# edgesata-v2.net
KiCad netlist of a schematic drawn in EAGLE
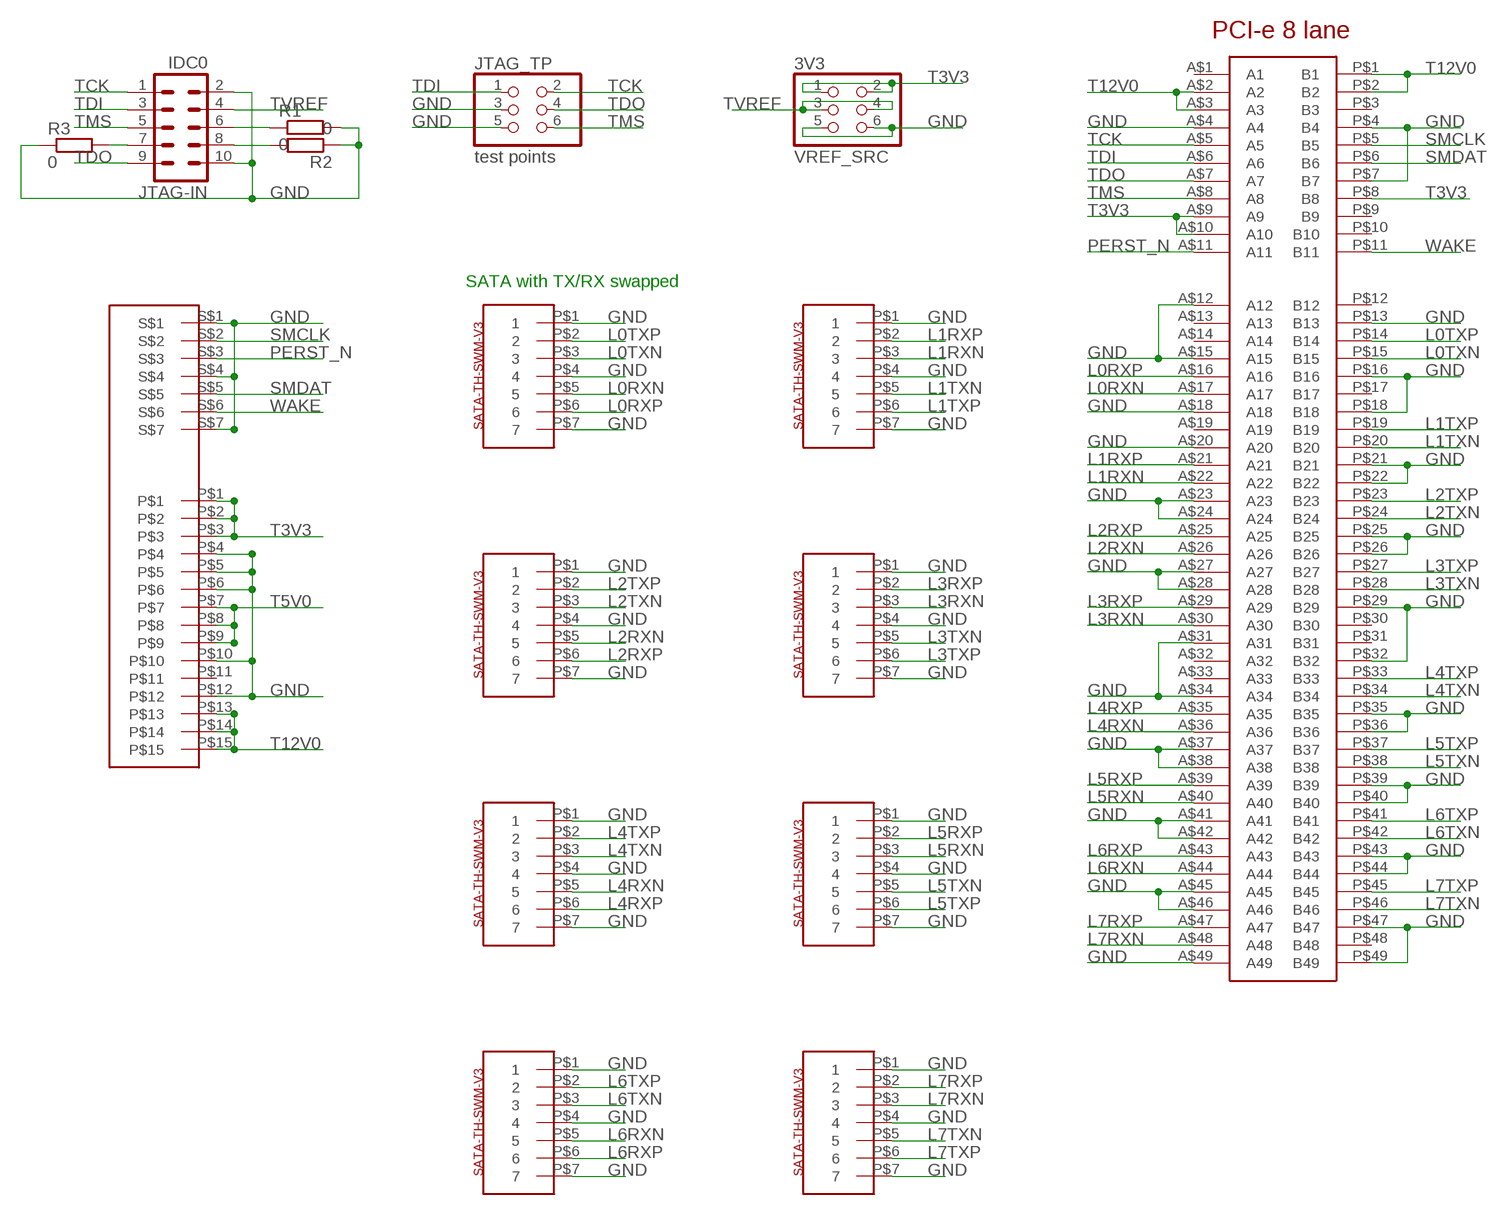
[diagram p0: schematic, sheet 1]

(export (version "E")
  (design (tool "Eeschema 10.0.6"))
  (components
    (comp (ref "3V3")
      (value "VREF_SRC")
      (footprint "eagle-import:2X03")
      (libsource (lib "eagle-import") (part "PINHD-2X3"))
    )
    (comp (ref "JTAG-IN")
      (value "IDC0")
      (footprint "eagle-import:MA05-2")
      (libsource (lib "eagle-import") (part "MA05-2"))
    )
    (comp (ref "JTAG_TP")
      (value "test points")
      (footprint "eagle-import:2X03")
      (libsource (lib "eagle-import") (part "PINHD-2X3"))
    )
    (comp (ref "LANE0")
      (value "SATA-TH-SWM-V3")
      (footprint "eagle-import:SATA-TH-SWM-V3")
      (libsource (lib "eagle-import") (part "SATA-TH-SWM-V3"))
    )
    (comp (ref "LANE1")
      (value "SATA-TH-SWM-V3")
      (footprint "eagle-import:SATA-TH-SWM-V3")
      (libsource (lib "eagle-import") (part "SATA-TH-SWM-V3"))
    )
    (comp (ref "LANE2")
      (value "SATA-TH-SWM-V3")
      (footprint "eagle-import:SATA-TH-SWM-V3")
      (libsource (lib "eagle-import") (part "SATA-TH-SWM-V3"))
    )
    (comp (ref "LANE3")
      (value "SATA-TH-SWM-V3")
      (footprint "eagle-import:SATA-TH-SWM-V3")
      (libsource (lib "eagle-import") (part "SATA-TH-SWM-V3"))
    )
    (comp (ref "LANE4")
      (value "SATA-TH-SWM-V3")
      (footprint "eagle-import:SATA-TH-SWM-V3")
      (libsource (lib "eagle-import") (part "SATA-TH-SWM-V3"))
    )
    (comp (ref "LANE5")
      (value "SATA-TH-SWM-V3")
      (footprint "eagle-import:SATA-TH-SWM-V3")
      (libsource (lib "eagle-import") (part "SATA-TH-SWM-V3"))
    )
    (comp (ref "LANE6")
      (value "SATA-TH-SWM-V3")
      (footprint "eagle-import:SATA-TH-SWM-V3")
      (libsource (lib "eagle-import") (part "SATA-TH-SWM-V3"))
    )
    (comp (ref "LANE7")
      (value "SATA-TH-SWM-V3")
      (footprint "eagle-import:SATA-TH-SWM-V3")
      (libsource (lib "eagle-import") (part "SATA-TH-SWM-V3"))
    )
    (comp (ref "R1")
      (value "0")
      (footprint "eagle-import:R0805W")
      (libsource (lib "eagle-import") (part "R-EU_R0805W"))
    )
    (comp (ref "R2")
      (value "0")
      (footprint "eagle-import:R0805W")
      (libsource (lib "eagle-import") (part "R-EU_R0805W"))
    )
    (comp (ref "R3")
      (value "0")
      (footprint "eagle-import:R0805W")
      (libsource (lib "eagle-import") (part "R-EU_R0805W"))
    )
    (comp (ref "U$1")
      (value "SATA-POWER-V1")
      (footprint "eagle-import:SATA-POWER-V1")
      (libsource (lib "eagle-import") (part "SATA-POWER-V1"))
    )
    (comp (ref "U$8")
      (value "PCIE-EDGE-8LANE-V1")
      (footprint "eagle-import:PCIE-EDGE-8LANE-V1")
      (libsource (lib "eagle-import") (part "PCIE-EDGE-8LANE-V1"))
    )
  )
  (nets
    (net (code "1") (name "/GND") (class "Default")
      (node (ref "3V3") (pin "5") (pinfunction "5_5") (pintype "passive"))
      (node (ref "3V3") (pin "6") (pinfunction "6_6") (pintype "passive"))
      (node (ref "JTAG-IN") (pin "10") (pinfunction "10_10") (pintype "passive"))
      (node (ref "JTAG-IN") (pin "2") (pinfunction "2_2") (pintype "passive"))
      (node (ref "JTAG_TP") (pin "3") (pinfunction "3_3") (pintype "passive"))
      (node (ref "JTAG_TP") (pin "5") (pinfunction "5_5") (pintype "passive"))
      (node (ref "LANE0") (pin "P$1") (pinfunction "1_P$1") (pintype "bidirectional"))
      (node (ref "LANE0") (pin "P$4") (pinfunction "4_P$4") (pintype "bidirectional"))
      (node (ref "LANE0") (pin "P$7") (pinfunction "7_P$7") (pintype "bidirectional"))
      (node (ref "LANE1") (pin "P$1") (pinfunction "1_P$1") (pintype "bidirectional"))
      (node (ref "LANE1") (pin "P$4") (pinfunction "4_P$4") (pintype "bidirectional"))
      (node (ref "LANE1") (pin "P$7") (pinfunction "7_P$7") (pintype "bidirectional"))
      (node (ref "LANE2") (pin "P$1") (pinfunction "1_P$1") (pintype "bidirectional"))
      (node (ref "LANE2") (pin "P$4") (pinfunction "4_P$4") (pintype "bidirectional"))
      (node (ref "LANE2") (pin "P$7") (pinfunction "7_P$7") (pintype "bidirectional"))
      (node (ref "LANE3") (pin "P$1") (pinfunction "1_P$1") (pintype "bidirectional"))
      (node (ref "LANE3") (pin "P$4") (pinfunction "4_P$4") (pintype "bidirectional"))
      (node (ref "LANE3") (pin "P$7") (pinfunction "7_P$7") (pintype "bidirectional"))
      (node (ref "LANE4") (pin "P$1") (pinfunction "1_P$1") (pintype "bidirectional"))
      (node (ref "LANE4") (pin "P$4") (pinfunction "4_P$4") (pintype "bidirectional"))
      (node (ref "LANE4") (pin "P$7") (pinfunction "7_P$7") (pintype "bidirectional"))
      (node (ref "LANE5") (pin "P$1") (pinfunction "1_P$1") (pintype "bidirectional"))
      (node (ref "LANE5") (pin "P$4") (pinfunction "4_P$4") (pintype "bidirectional"))
      (node (ref "LANE5") (pin "P$7") (pinfunction "7_P$7") (pintype "bidirectional"))
      (node (ref "LANE6") (pin "P$1") (pinfunction "1_P$1") (pintype "bidirectional"))
      (node (ref "LANE6") (pin "P$4") (pinfunction "4_P$4") (pintype "bidirectional"))
      (node (ref "LANE6") (pin "P$7") (pinfunction "7_P$7") (pintype "bidirectional"))
      (node (ref "LANE7") (pin "P$1") (pinfunction "1_P$1") (pintype "bidirectional"))
      (node (ref "LANE7") (pin "P$4") (pinfunction "4_P$4") (pintype "bidirectional"))
      (node (ref "LANE7") (pin "P$7") (pinfunction "7_P$7") (pintype "bidirectional"))
      (node (ref "R1") (pin "2") (pinfunction "2_2") (pintype "passive"))
      (node (ref "R2") (pin "1") (pinfunction "1_1") (pintype "passive"))
      (node (ref "R3") (pin "1") (pinfunction "1_1") (pintype "passive"))
      (node (ref "U$1") (pin "P$10") (pinfunction "P$10_P$10") (pintype "bidirectional"))
      (node (ref "U$1") (pin "P$12") (pinfunction "P$12_P$12") (pintype "bidirectional"))
      (node (ref "U$1") (pin "P$4") (pinfunction "P$4_P$4") (pintype "bidirectional"))
      (node (ref "U$1") (pin "P$5") (pinfunction "P$5_P$5") (pintype "bidirectional"))
      (node (ref "U$1") (pin "P$6") (pinfunction "P$6_P$6") (pintype "bidirectional"))
      (node (ref "U$1") (pin "S$1") (pinfunction "S$1_S$1") (pintype "bidirectional"))
      (node (ref "U$1") (pin "S$4") (pinfunction "S$4_S$4") (pintype "bidirectional"))
      (node (ref "U$1") (pin "S$7") (pinfunction "S$7_S$7") (pintype "bidirectional"))
      (node (ref "U$8") (pin "A$12") (pinfunction "A12_A$12") (pintype "bidirectional"))
      (node (ref "U$8") (pin "A$15") (pinfunction "A15_A$15") (pintype "bidirectional"))
      (node (ref "U$8") (pin "A$18") (pinfunction "A18_A$18") (pintype "bidirectional"))
      (node (ref "U$8") (pin "A$20") (pinfunction "A20_A$20") (pintype "bidirectional"))
      (node (ref "U$8") (pin "A$23") (pinfunction "A23_A$23") (pintype "bidirectional"))
      (node (ref "U$8") (pin "A$24") (pinfunction "A24_A$24") (pintype "bidirectional"))
      (node (ref "U$8") (pin "A$27") (pinfunction "A27_A$27") (pintype "bidirectional"))
      (node (ref "U$8") (pin "A$28") (pinfunction "A28_A$28") (pintype "bidirectional"))
      (node (ref "U$8") (pin "A$31") (pinfunction "A31_A$31") (pintype "bidirectional"))
      (node (ref "U$8") (pin "A$34") (pinfunction "A34_A$34") (pintype "bidirectional"))
      (node (ref "U$8") (pin "A$37") (pinfunction "A37_A$37") (pintype "bidirectional"))
      (node (ref "U$8") (pin "A$38") (pinfunction "A38_A$38") (pintype "bidirectional"))
      (node (ref "U$8") (pin "A$4") (pinfunction "A4_A$4") (pintype "bidirectional"))
      (node (ref "U$8") (pin "A$41") (pinfunction "A41_A$41") (pintype "bidirectional"))
      (node (ref "U$8") (pin "A$42") (pinfunction "A42_A$42") (pintype "bidirectional"))
      (node (ref "U$8") (pin "A$45") (pinfunction "A45_A$45") (pintype "bidirectional"))
      (node (ref "U$8") (pin "A$46") (pinfunction "A46_A$46") (pintype "bidirectional"))
      (node (ref "U$8") (pin "A$49") (pinfunction "A49_A$49") (pintype "bidirectional"))
      (node (ref "U$8") (pin "P$13") (pinfunction "B13_P$13") (pintype "bidirectional"))
      (node (ref "U$8") (pin "P$16") (pinfunction "B16_P$16") (pintype "bidirectional"))
      (node (ref "U$8") (pin "P$18") (pinfunction "B18_P$18") (pintype "bidirectional"))
      (node (ref "U$8") (pin "P$21") (pinfunction "B21_P$21") (pintype "bidirectional"))
      (node (ref "U$8") (pin "P$22") (pinfunction "B22_P$22") (pintype "bidirectional"))
      (node (ref "U$8") (pin "P$25") (pinfunction "B25_P$25") (pintype "bidirectional"))
      (node (ref "U$8") (pin "P$26") (pinfunction "B26_P$26") (pintype "bidirectional"))
      (node (ref "U$8") (pin "P$29") (pinfunction "B29_P$29") (pintype "bidirectional"))
      (node (ref "U$8") (pin "P$32") (pinfunction "B32_P$32") (pintype "bidirectional"))
      (node (ref "U$8") (pin "P$35") (pinfunction "B35_P$35") (pintype "bidirectional"))
      (node (ref "U$8") (pin "P$36") (pinfunction "B36_P$36") (pintype "bidirectional"))
      (node (ref "U$8") (pin "P$39") (pinfunction "B39_P$39") (pintype "bidirectional"))
      (node (ref "U$8") (pin "P$4") (pinfunction "B4_P$4") (pintype "bidirectional"))
      (node (ref "U$8") (pin "P$40") (pinfunction "B40_P$40") (pintype "bidirectional"))
      (node (ref "U$8") (pin "P$43") (pinfunction "B43_P$43") (pintype "bidirectional"))
      (node (ref "U$8") (pin "P$44") (pinfunction "B44_P$44") (pintype "bidirectional"))
      (node (ref "U$8") (pin "P$47") (pinfunction "B47_P$47") (pintype "bidirectional"))
      (node (ref "U$8") (pin "P$49") (pinfunction "B49_P$49") (pintype "bidirectional"))
      (node (ref "U$8") (pin "P$7") (pinfunction "B7_P$7") (pintype "bidirectional"))
    )
    (net (code "2") (name "/L0RXN") (class "Default")
      (node (ref "LANE0") (pin "P$5") (pinfunction "5_P$5") (pintype "bidirectional"))
      (node (ref "U$8") (pin "A$17") (pinfunction "A17_A$17") (pintype "bidirectional"))
    )
    (net (code "3") (name "/L0RXP") (class "Default")
      (node (ref "LANE0") (pin "P$6") (pinfunction "6_P$6") (pintype "bidirectional"))
      (node (ref "U$8") (pin "A$16") (pinfunction "A16_A$16") (pintype "bidirectional"))
    )
    (net (code "4") (name "/L0TXN") (class "Default")
      (node (ref "LANE0") (pin "P$3") (pinfunction "3_P$3") (pintype "bidirectional"))
      (node (ref "U$8") (pin "P$15") (pinfunction "B15_P$15") (pintype "bidirectional"))
    )
    (net (code "5") (name "/L0TXP") (class "Default")
      (node (ref "LANE0") (pin "P$2") (pinfunction "2_P$2") (pintype "bidirectional"))
      (node (ref "U$8") (pin "P$14") (pinfunction "B14_P$14") (pintype "bidirectional"))
    )
    (net (code "6") (name "/L1RXN") (class "Default")
      (node (ref "LANE1") (pin "P$3") (pinfunction "3_P$3") (pintype "bidirectional"))
      (node (ref "U$8") (pin "A$22") (pinfunction "A22_A$22") (pintype "bidirectional"))
    )
    (net (code "7") (name "/L1RXP") (class "Default")
      (node (ref "LANE1") (pin "P$2") (pinfunction "2_P$2") (pintype "bidirectional"))
      (node (ref "U$8") (pin "A$21") (pinfunction "A21_A$21") (pintype "bidirectional"))
    )
    (net (code "8") (name "/L1TXN") (class "Default")
      (node (ref "LANE1") (pin "P$5") (pinfunction "5_P$5") (pintype "bidirectional"))
      (node (ref "U$8") (pin "P$20") (pinfunction "B20_P$20") (pintype "bidirectional"))
    )
    (net (code "9") (name "/L1TXP") (class "Default")
      (node (ref "LANE1") (pin "P$6") (pinfunction "6_P$6") (pintype "bidirectional"))
      (node (ref "U$8") (pin "P$19") (pinfunction "B19_P$19") (pintype "bidirectional"))
    )
    (net (code "10") (name "/L2RXN") (class "Default")
      (node (ref "LANE2") (pin "P$5") (pinfunction "5_P$5") (pintype "bidirectional"))
      (node (ref "U$8") (pin "A$26") (pinfunction "A26_A$26") (pintype "bidirectional"))
    )
    (net (code "11") (name "/L2RXP") (class "Default")
      (node (ref "LANE2") (pin "P$6") (pinfunction "6_P$6") (pintype "bidirectional"))
      (node (ref "U$8") (pin "A$25") (pinfunction "A25_A$25") (pintype "bidirectional"))
    )
    (net (code "12") (name "/L2TXN") (class "Default")
      (node (ref "LANE2") (pin "P$3") (pinfunction "3_P$3") (pintype "bidirectional"))
      (node (ref "U$8") (pin "P$24") (pinfunction "B24_P$24") (pintype "bidirectional"))
    )
    (net (code "13") (name "/L2TXP") (class "Default")
      (node (ref "LANE2") (pin "P$2") (pinfunction "2_P$2") (pintype "bidirectional"))
      (node (ref "U$8") (pin "P$23") (pinfunction "B23_P$23") (pintype "bidirectional"))
    )
    (net (code "14") (name "/L3RXN") (class "Default")
      (node (ref "LANE3") (pin "P$3") (pinfunction "3_P$3") (pintype "bidirectional"))
      (node (ref "U$8") (pin "A$30") (pinfunction "A30_A$30") (pintype "bidirectional"))
    )
    (net (code "15") (name "/L3RXP") (class "Default")
      (node (ref "LANE3") (pin "P$2") (pinfunction "2_P$2") (pintype "bidirectional"))
      (node (ref "U$8") (pin "A$29") (pinfunction "A29_A$29") (pintype "bidirectional"))
    )
    (net (code "16") (name "/L3TXN") (class "Default")
      (node (ref "LANE3") (pin "P$5") (pinfunction "5_P$5") (pintype "bidirectional"))
      (node (ref "U$8") (pin "P$28") (pinfunction "B28_P$28") (pintype "bidirectional"))
    )
    (net (code "17") (name "/L3TXP") (class "Default")
      (node (ref "LANE3") (pin "P$6") (pinfunction "6_P$6") (pintype "bidirectional"))
      (node (ref "U$8") (pin "P$27") (pinfunction "B27_P$27") (pintype "bidirectional"))
    )
    (net (code "18") (name "/L4RXN") (class "Default")
      (node (ref "LANE4") (pin "P$5") (pinfunction "5_P$5") (pintype "bidirectional"))
      (node (ref "U$8") (pin "A$36") (pinfunction "A36_A$36") (pintype "bidirectional"))
    )
    (net (code "19") (name "/L4RXP") (class "Default")
      (node (ref "LANE4") (pin "P$6") (pinfunction "6_P$6") (pintype "bidirectional"))
      (node (ref "U$8") (pin "A$35") (pinfunction "A35_A$35") (pintype "bidirectional"))
    )
    (net (code "20") (name "/L4TXN") (class "Default")
      (node (ref "LANE4") (pin "P$3") (pinfunction "3_P$3") (pintype "bidirectional"))
      (node (ref "U$8") (pin "P$34") (pinfunction "B34_P$34") (pintype "bidirectional"))
    )
    (net (code "21") (name "/L4TXP") (class "Default")
      (node (ref "LANE4") (pin "P$2") (pinfunction "2_P$2") (pintype "bidirectional"))
      (node (ref "U$8") (pin "P$33") (pinfunction "B33_P$33") (pintype "bidirectional"))
    )
    (net (code "22") (name "/L5RXN") (class "Default")
      (node (ref "LANE5") (pin "P$3") (pinfunction "3_P$3") (pintype "bidirectional"))
      (node (ref "U$8") (pin "A$40") (pinfunction "A40_A$40") (pintype "bidirectional"))
    )
    (net (code "23") (name "/L5RXP") (class "Default")
      (node (ref "LANE5") (pin "P$2") (pinfunction "2_P$2") (pintype "bidirectional"))
      (node (ref "U$8") (pin "A$39") (pinfunction "A39_A$39") (pintype "bidirectional"))
    )
    (net (code "24") (name "/L5TXN") (class "Default")
      (node (ref "LANE5") (pin "P$5") (pinfunction "5_P$5") (pintype "bidirectional"))
      (node (ref "U$8") (pin "P$38") (pinfunction "B38_P$38") (pintype "bidirectional"))
    )
    (net (code "25") (name "/L5TXP") (class "Default")
      (node (ref "LANE5") (pin "P$6") (pinfunction "6_P$6") (pintype "bidirectional"))
      (node (ref "U$8") (pin "P$37") (pinfunction "B37_P$37") (pintype "bidirectional"))
    )
    (net (code "26") (name "/L6RXN") (class "Default")
      (node (ref "LANE6") (pin "P$5") (pinfunction "5_P$5") (pintype "bidirectional"))
      (node (ref "U$8") (pin "A$44") (pinfunction "A44_A$44") (pintype "bidirectional"))
    )
    (net (code "27") (name "/L6RXP") (class "Default")
      (node (ref "LANE6") (pin "P$6") (pinfunction "6_P$6") (pintype "bidirectional"))
      (node (ref "U$8") (pin "A$43") (pinfunction "A43_A$43") (pintype "bidirectional"))
    )
    (net (code "28") (name "/L6TXN") (class "Default")
      (node (ref "LANE6") (pin "P$3") (pinfunction "3_P$3") (pintype "bidirectional"))
      (node (ref "U$8") (pin "P$42") (pinfunction "B42_P$42") (pintype "bidirectional"))
    )
    (net (code "29") (name "/L6TXP") (class "Default")
      (node (ref "LANE6") (pin "P$2") (pinfunction "2_P$2") (pintype "bidirectional"))
      (node (ref "U$8") (pin "P$41") (pinfunction "B41_P$41") (pintype "bidirectional"))
    )
    (net (code "30") (name "/L7RXN") (class "Default")
      (node (ref "LANE7") (pin "P$3") (pinfunction "3_P$3") (pintype "bidirectional"))
      (node (ref "U$8") (pin "A$48") (pinfunction "A48_A$48") (pintype "bidirectional"))
    )
    (net (code "31") (name "/L7RXP") (class "Default")
      (node (ref "LANE7") (pin "P$2") (pinfunction "2_P$2") (pintype "bidirectional"))
      (node (ref "U$8") (pin "A$47") (pinfunction "A47_A$47") (pintype "bidirectional"))
    )
    (net (code "32") (name "/L7TXN") (class "Default")
      (node (ref "LANE7") (pin "P$5") (pinfunction "5_P$5") (pintype "bidirectional"))
      (node (ref "U$8") (pin "P$46") (pinfunction "B46_P$46") (pintype "bidirectional"))
    )
    (net (code "33") (name "/L7TXP") (class "Default")
      (node (ref "LANE7") (pin "P$6") (pinfunction "6_P$6") (pintype "bidirectional"))
      (node (ref "U$8") (pin "P$45") (pinfunction "B45_P$45") (pintype "bidirectional"))
    )
    (net (code "34") (name "/PERST_N") (class "Default")
      (node (ref "U$1") (pin "S$3") (pinfunction "S$3_S$3") (pintype "bidirectional"))
      (node (ref "U$8") (pin "A$11") (pinfunction "A11_A$11") (pintype "bidirectional"))
    )
    (net (code "35") (name "/SMCLK") (class "Default")
      (node (ref "U$1") (pin "S$2") (pinfunction "S$2_S$2") (pintype "bidirectional"))
      (node (ref "U$8") (pin "P$5") (pinfunction "B5_P$5") (pintype "bidirectional"))
    )
    (net (code "36") (name "/SMDAT") (class "Default")
      (node (ref "U$1") (pin "S$5") (pinfunction "S$5_S$5") (pintype "bidirectional"))
      (node (ref "U$8") (pin "P$6") (pinfunction "B6_P$6") (pintype "bidirectional"))
    )
    (net (code "37") (name "/T3V3") (class "Default")
      (node (ref "3V3") (pin "1") (pinfunction "1_1") (pintype "passive"))
      (node (ref "3V3") (pin "2") (pinfunction "2_2") (pintype "passive"))
      (node (ref "U$1") (pin "P$1") (pinfunction "P$1_P$1") (pintype "bidirectional"))
      (node (ref "U$1") (pin "P$2") (pinfunction "P$2_P$2") (pintype "bidirectional"))
      (node (ref "U$1") (pin "P$3") (pinfunction "P$3_P$3") (pintype "bidirectional"))
      (node (ref "U$8") (pin "A$10") (pinfunction "A10_A$10") (pintype "bidirectional"))
      (node (ref "U$8") (pin "A$9") (pinfunction "A9_A$9") (pintype "bidirectional"))
      (node (ref "U$8") (pin "P$8") (pinfunction "B8_P$8") (pintype "bidirectional"))
    )
    (net (code "38") (name "/T5V0") (class "Default")
      (node (ref "U$1") (pin "P$7") (pinfunction "P$7_P$7") (pintype "bidirectional"))
      (node (ref "U$1") (pin "P$8") (pinfunction "P$8_P$8") (pintype "bidirectional"))
      (node (ref "U$1") (pin "P$9") (pinfunction "P$9_P$9") (pintype "bidirectional"))
    )
    (net (code "39") (name "/T12V0") (class "Default")
      (node (ref "U$1") (pin "P$13") (pinfunction "P$13_P$13") (pintype "bidirectional"))
      (node (ref "U$1") (pin "P$14") (pinfunction "P$14_P$14") (pintype "bidirectional"))
      (node (ref "U$1") (pin "P$15") (pinfunction "P$15_P$15") (pintype "bidirectional"))
      (node (ref "U$8") (pin "A$2") (pinfunction "A2_A$2") (pintype "bidirectional"))
      (node (ref "U$8") (pin "A$3") (pinfunction "A3_A$3") (pintype "bidirectional"))
      (node (ref "U$8") (pin "P$1") (pinfunction "B1_P$1") (pintype "bidirectional"))
      (node (ref "U$8") (pin "P$2") (pinfunction "B2_P$2") (pintype "bidirectional"))
    )
    (net (code "40") (name "/TCK") (class "Default")
      (node (ref "JTAG-IN") (pin "1") (pinfunction "1_1") (pintype "passive"))
      (node (ref "JTAG_TP") (pin "2") (pinfunction "2_2") (pintype "passive"))
      (node (ref "U$8") (pin "A$5") (pinfunction "A5_A$5") (pintype "bidirectional"))
    )
    (net (code "41") (name "/TDI") (class "Default")
      (node (ref "JTAG-IN") (pin "3") (pinfunction "3_3") (pintype "passive"))
      (node (ref "JTAG_TP") (pin "1") (pinfunction "1_1") (pintype "passive"))
      (node (ref "U$8") (pin "A$6") (pinfunction "A6_A$6") (pintype "bidirectional"))
    )
    (net (code "42") (name "/TDO") (class "Default")
      (node (ref "JTAG-IN") (pin "9") (pinfunction "9_9") (pintype "passive"))
      (node (ref "JTAG_TP") (pin "4") (pinfunction "4_4") (pintype "passive"))
      (node (ref "U$8") (pin "A$7") (pinfunction "A7_A$7") (pintype "bidirectional"))
    )
    (net (code "43") (name "/TMS") (class "Default")
      (node (ref "JTAG-IN") (pin "5") (pinfunction "5_5") (pintype "passive"))
      (node (ref "JTAG_TP") (pin "6") (pinfunction "6_6") (pintype "passive"))
      (node (ref "U$8") (pin "A$8") (pinfunction "A8_A$8") (pintype "bidirectional"))
    )
    (net (code "44") (name "/TVREF") (class "Default")
      (node (ref "3V3") (pin "3") (pinfunction "3_3") (pintype "passive"))
      (node (ref "3V3") (pin "4") (pinfunction "4_4") (pintype "passive"))
      (node (ref "JTAG-IN") (pin "4") (pinfunction "4_4") (pintype "passive"))
    )
    (net (code "45") (name "/WAKE") (class "Default")
      (node (ref "U$1") (pin "S$6") (pinfunction "S$6_S$6") (pintype "bidirectional"))
      (node (ref "U$8") (pin "P$11") (pinfunction "B11_P$11") (pintype "bidirectional"))
    )
    (net (code "46") (name "Net-(JTAG-IN-Pad6)") (class "Default")
      (node (ref "JTAG-IN") (pin "6") (pinfunction "6_6") (pintype "passive"))
      (node (ref "R1") (pin "1") (pinfunction "1_1") (pintype "passive"))
    )
    (net (code "47") (name "Net-(JTAG-IN-Pad7)") (class "Default")
      (node (ref "JTAG-IN") (pin "7") (pinfunction "7_7") (pintype "passive"))
      (node (ref "R3") (pin "2") (pinfunction "2_2") (pintype "passive"))
    )
    (net (code "48") (name "Net-(JTAG-IN-Pad8)") (class "Default")
      (node (ref "JTAG-IN") (pin "8") (pinfunction "8_8") (pintype "passive"))
      (node (ref "R2") (pin "2") (pinfunction "2_2") (pintype "passive"))
    )
    (net (code "49") (name "unconnected-(U$1-PadP$11)") (class "Default")
      (node (ref "U$1") (pin "P$11") (pinfunction "P$11_P$11") (pintype "no_connect"))
    )
    (net (code "50") (name "unconnected-(U$8-A1-PadA$1)") (class "Default")
      (node (ref "U$8") (pin "A$1") (pinfunction "A1_A$1") (pintype "bidirectional"))
    )
    (net (code "51") (name "unconnected-(U$8-A13-PadA$13)") (class "Default")
      (node (ref "U$8") (pin "A$13") (pinfunction "A13_A$13") (pintype "bidirectional"))
    )
    (net (code "52") (name "unconnected-(U$8-A14-PadA$14)") (class "Default")
      (node (ref "U$8") (pin "A$14") (pinfunction "A14_A$14") (pintype "bidirectional"))
    )
    (net (code "53") (name "unconnected-(U$8-A19-PadA$19)") (class "Default")
      (node (ref "U$8") (pin "A$19") (pinfunction "A19_A$19") (pintype "bidirectional"))
    )
    (net (code "54") (name "unconnected-(U$8-A32-PadA$32)") (class "Default")
      (node (ref "U$8") (pin "A$32") (pinfunction "A32_A$32") (pintype "bidirectional"))
    )
    (net (code "55") (name "unconnected-(U$8-A33-PadA$33)") (class "Default")
      (node (ref "U$8") (pin "A$33") (pinfunction "A33_A$33") (pintype "bidirectional"))
    )
    (net (code "56") (name "unconnected-(U$8-B3-PadP$3)") (class "Default")
      (node (ref "U$8") (pin "P$3") (pinfunction "B3_P$3") (pintype "bidirectional"))
    )
    (net (code "57") (name "unconnected-(U$8-B9-PadP$9)") (class "Default")
      (node (ref "U$8") (pin "P$9") (pinfunction "B9_P$9") (pintype "bidirectional"))
    )
    (net (code "58") (name "unconnected-(U$8-B10-PadP$10)") (class "Default")
      (node (ref "U$8") (pin "P$10") (pinfunction "B10_P$10") (pintype "bidirectional"))
    )
    (net (code "59") (name "unconnected-(U$8-B12-PadP$12)") (class "Default")
      (node (ref "U$8") (pin "P$12") (pinfunction "B12_P$12") (pintype "bidirectional"))
    )
    (net (code "60") (name "unconnected-(U$8-B17-PadP$17)") (class "Default")
      (node (ref "U$8") (pin "P$17") (pinfunction "B17_P$17") (pintype "bidirectional"))
    )
    (net (code "61") (name "unconnected-(U$8-B30-PadP$30)") (class "Default")
      (node (ref "U$8") (pin "P$30") (pinfunction "B30_P$30") (pintype "bidirectional"))
    )
    (net (code "62") (name "unconnected-(U$8-B31-PadP$31)") (class "Default")
      (node (ref "U$8") (pin "P$31") (pinfunction "B31_P$31") (pintype "bidirectional"))
    )
    (net (code "63") (name "unconnected-(U$8-B48-PadP$48)") (class "Default")
      (node (ref "U$8") (pin "P$48") (pinfunction "B48_P$48") (pintype "bidirectional"))
    )
  )
)
